# design.net
KiCad netlist of a schematic drawn in Altium Designer
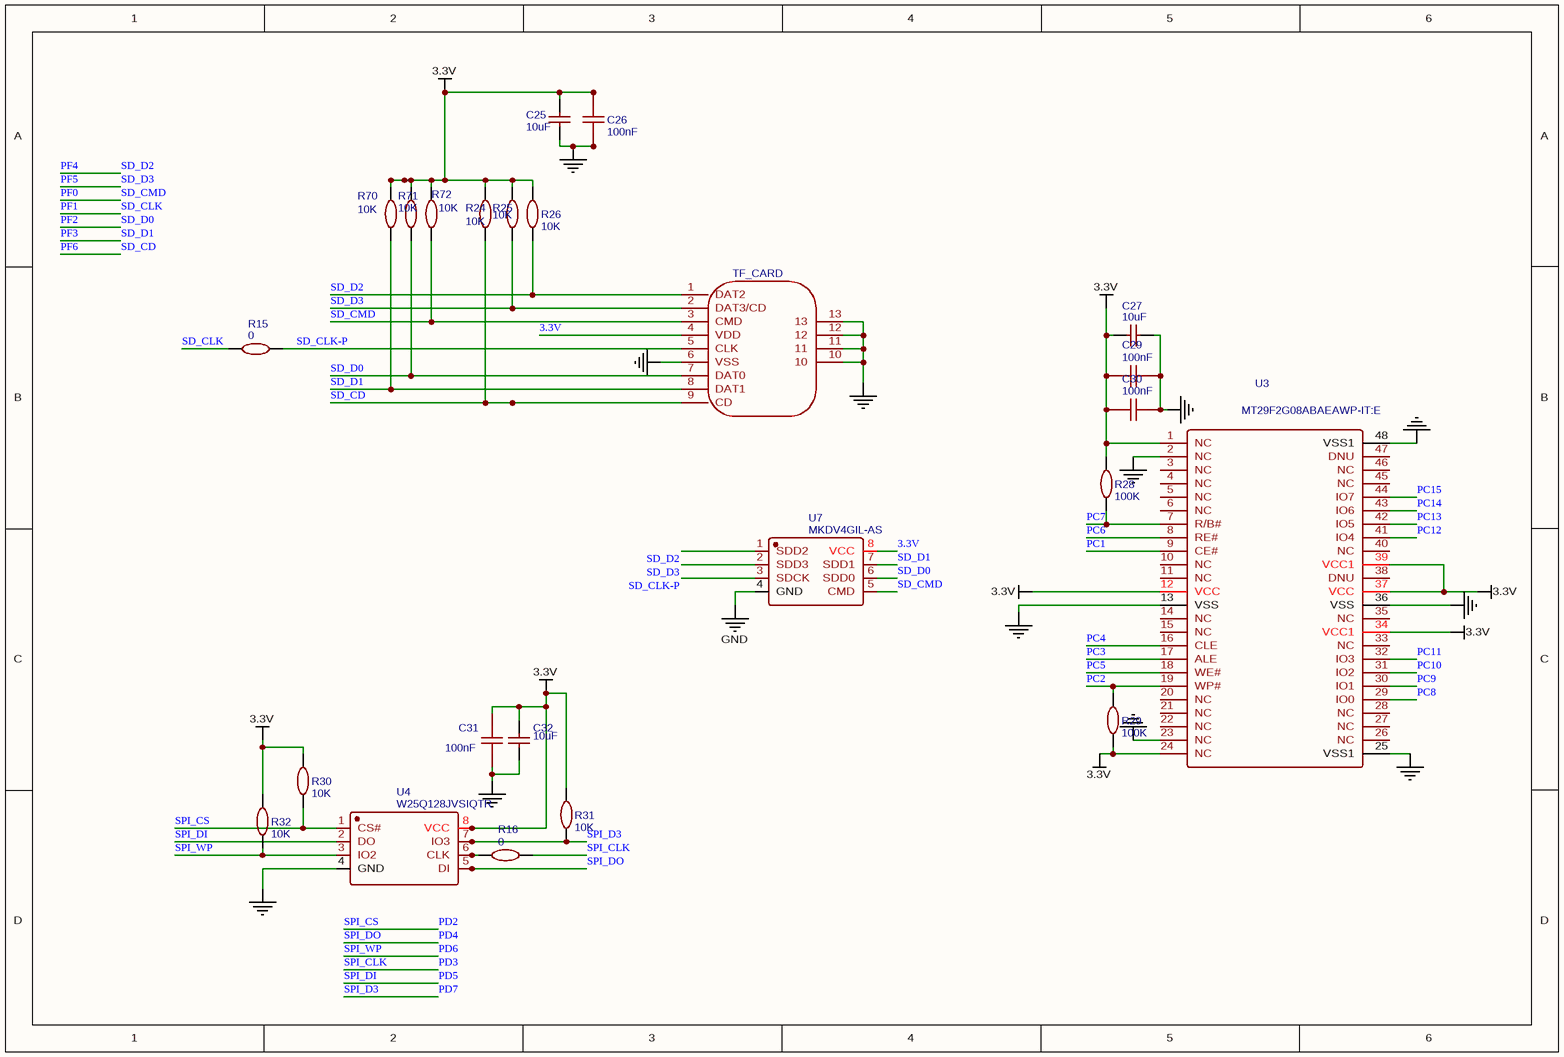
[diagram p0: 存储单元.schdoc]

(export (version "E")
  (design (tool "Eeschema 10.0.6"))
  (components
    (comp (ref "C25")
      (value "10uF")
      (footprint "0805")
      (fields
        (field (name "BOM_MANUFACTURER PART") "CL21A106KAYNNNE")
        (field (name "BOM_SUPPLIER PART") "C15850")
      )
      (libsource (lib "altium-import") (part "root_1_10uF_"))
    )
    (comp (ref "C26")
      (value "100nF")
      (footprint "0603")
      (fields
        (field (name "BOM_MANUFACTURER PART") "CC0603KRX7R9BB104")
        (field (name "BOM_SUPPLIER PART") "C14663")
      )
      (libsource (lib "altium-import") (part "root_1_100nF_"))
    )
    (comp (ref "C27")
      (value "10uF")
      (footprint "0805")
      (fields
        (field (name "BOM_MANUFACTURER PART") "CL21A106KAYNNNE")
        (field (name "BOM_SUPPLIER PART") "C15850")
      )
      (libsource (lib "altium-import") (part "root_2_10uF_"))
    )
    (comp (ref "C29")
      (value "100nF")
      (footprint "0603")
      (fields
        (field (name "BOM_MANUFACTURER PART") "CC0603KRX7R9BB104")
        (field (name "BOM_SUPPLIER PART") "C14663")
      )
      (libsource (lib "altium-import") (part "root_0_100nF_"))
    )
    (comp (ref "C30")
      (value "100nF")
      (footprint "0603")
      (fields
        (field (name "BOM_MANUFACTURER PART") "CC0603KRX7R9BB104")
        (field (name "BOM_SUPPLIER PART") "C14663")
      )
      (libsource (lib "altium-import") (part "root_2_100nF_"))
    )
    (comp (ref "C31")
      (value "100nF")
      (footprint "0603")
      (fields
        (field (name "BOM_MANUFACTURER PART") "CC0603KRX7R9BB104")
        (field (name "BOM_SUPPLIER PART") "C14663")
      )
      (libsource (lib "altium-import") (part "root_3_100nF_"))
    )
    (comp (ref "C32")
      (value "10uF")
      (footprint "0805")
      (fields
        (field (name "BOM_MANUFACTURER PART") "CL21A106KAYNNNE")
        (field (name "BOM_SUPPLIER PART") "C15850")
      )
      (libsource (lib "altium-import") (part "root_3_10uF_"))
    )
    (comp (ref "R15")
      (value "0")
      (footprint "0603")
      (fields
        (field (name "BOM_MANUFACTURER PART") "0603WAF0000T5E")
        (field (name "BOM_SUPPLIER PART") "C21189")
      )
      (libsource (lib "altium-import") (part "root_0_0_"))
    )
    (comp (ref "R16")
      (value "0")
      (footprint "0603")
      (fields
        (field (name "BOM_MANUFACTURER PART") "0603WAF0000T5E")
        (field (name "BOM_SUPPLIER PART") "C21189")
      )
      (libsource (lib "altium-import") (part "root_0_0_"))
    )
    (comp (ref "R24")
      (value "10K")
      (footprint "0603")
      (fields
        (field (name "BOM_MANUFACTURER PART") "0603WAF1002T5E")
        (field (name "BOM_SUPPLIER PART") "C25804")
      )
      (libsource (lib "altium-import") (part "root_1_10K_"))
    )
    (comp (ref "R25")
      (value "10K")
      (footprint "0603")
      (fields
        (field (name "BOM_MANUFACTURER PART") "0603WAF1002T5E")
        (field (name "BOM_SUPPLIER PART") "C25804")
      )
      (libsource (lib "altium-import") (part "root_1_10K_"))
    )
    (comp (ref "R26")
      (value "10K")
      (footprint "0603")
      (fields
        (field (name "BOM_MANUFACTURER PART") "0603WAF1002T5E")
        (field (name "BOM_SUPPLIER PART") "C25804")
      )
      (libsource (lib "altium-import") (part "root_1_10K_"))
    )
    (comp (ref "R28")
      (value "100K")
      (footprint "0603")
      (fields
        (field (name "BOM_MANUFACTURER PART") "0603WAF1003T5E")
        (field (name "BOM_SUPPLIER PART") "C25803")
      )
      (libsource (lib "altium-import") (part "root_1_100K_"))
    )
    (comp (ref "R29")
      (value "100K")
      (footprint "0603")
      (fields
        (field (name "BOM_MANUFACTURER PART") "0603WAF1003T5E")
        (field (name "BOM_SUPPLIER PART") "C25803")
      )
      (libsource (lib "altium-import") (part "root_1_100K_"))
    )
    (comp (ref "R30")
      (value "10K")
      (footprint "0603")
      (fields
        (field (name "BOM_MANUFACTURER PART") "0603WAF1002T5E")
        (field (name "BOM_SUPPLIER PART") "C25804")
      )
      (libsource (lib "altium-import") (part "root_1_10K_"))
    )
    (comp (ref "R31")
      (value "10K")
      (footprint "0603")
      (fields
        (field (name "BOM_MANUFACTURER PART") "0603WAF1002T5E")
        (field (name "BOM_SUPPLIER PART") "C25804")
      )
      (libsource (lib "altium-import") (part "root_1_10K_"))
    )
    (comp (ref "R32")
      (value "10K")
      (footprint "0603")
      (fields
        (field (name "BOM_MANUFACTURER PART") "0603WAF1002T5E")
        (field (name "BOM_SUPPLIER PART") "C25804")
      )
      (libsource (lib "altium-import") (part "root_1_10K_"))
    )
    (comp (ref "R70")
      (value "10K")
      (footprint "0603")
      (fields
        (field (name "BOM_MANUFACTURER PART") "0603WAF1002T5E")
        (field (name "BOM_SUPPLIER PART") "C25804")
      )
      (libsource (lib "altium-import") (part "root_1_10K_"))
    )
    (comp (ref "R71")
      (value "10K")
      (footprint "0603")
      (fields
        (field (name "BOM_MANUFACTURER PART") "0603WAF1002T5E")
        (field (name "BOM_SUPPLIER PART") "C25804")
      )
      (libsource (lib "altium-import") (part "root_1_10K_"))
    )
    (comp (ref "R72")
      (value "10K")
      (footprint "0603")
      (fields
        (field (name "BOM_MANUFACTURER PART") "0603WAF1002T5E")
        (field (name "BOM_SUPPLIER PART") "C25804")
      )
      (libsource (lib "altium-import") (part "root_1_10K_"))
    )
    (comp (ref "TF_CARD1")
      (value "TF_CARD")
      (footprint "TF-115_MRS")
      (fields
        (field (name "BOM_MANUFACTURER PART") "?")
        (field (name "BOM_SUPPLIER PART") "undefined")
        (field (name "CONTRIBUTOR") "ration")
      )
      (libsource (lib "altium-import") (part "root_0_TF_CARD_"))
    )
    (comp (ref "U3")
      (value "MT29F2G08ABAEAWP-IT:E")
      (footprint "TSOP-48")
      (fields (field (name "BOM_SUPPLIER PART") "C110896") (field (name "CONTRIBUTOR") "LCSC"))
      (libsource (lib "altium-import") (part "root_0_MT29F2G08ABAEAWP-IT{colon}E_"))
    )
    (comp (ref "U4")
      (value "W25Q128JVSIQTR")
      (footprint "SOIC-8_208MIL")
      (fields (field (name "BOM_SUPPLIER PART") "C97521"))
      (libsource (lib "altium-import") (part "root_0_W25Q128JVSIQTR_"))
    )
    (comp (ref "U7")
      (value "MKDV4GIL-AS")
      (footprint "LGA-8_8PIN-L6.10-W8.10-PITCH0.65-TL")
      (fields (field (name "BOM_SUPPLIER PART") "C379093") (field (name "CONTRIBUTOR") "LCSC"))
      (libsource (lib "altium-import") (part "root_0_MKDV4GIL-AS_"))
    )
  )
  (nets
    (net (code "1") (name "/PC1") (class "Default")
      (node (ref "U3") (pin "9") (pinfunction "CE#_9") (pintype "passive"))
    )
    (net (code "2") (name "/PC2") (class "Default")
      (node (ref "R29") (pin "2") (pinfunction "2_2") (pintype "passive"))
      (node (ref "U3") (pin "19") (pinfunction "WP#_19") (pintype "passive"))
    )
    (net (code "3") (name "/PC3") (class "Default")
      (node (ref "U3") (pin "17") (pinfunction "ALE_17") (pintype "passive"))
    )
    (net (code "4") (name "/PC4") (class "Default")
      (node (ref "U3") (pin "16") (pinfunction "CLE_16") (pintype "passive"))
    )
    (net (code "5") (name "/PC5") (class "Default")
      (node (ref "U3") (pin "18") (pinfunction "WE#_18") (pintype "passive"))
    )
    (net (code "6") (name "/PC6") (class "Default")
      (node (ref "U3") (pin "8") (pinfunction "RE#_8") (pintype "passive"))
    )
    (net (code "7") (name "/PC7") (class "Default")
      (node (ref "R28") (pin "1") (pinfunction "1_1") (pintype "passive"))
      (node (ref "U3") (pin "7") (pinfunction "R/B#_7") (pintype "passive"))
    )
    (net (code "8") (name "/PC8") (class "Default")
      (node (ref "U3") (pin "29") (pinfunction "IO0_29") (pintype "passive"))
    )
    (net (code "9") (name "/PC9") (class "Default")
      (node (ref "U3") (pin "30") (pinfunction "IO1_30") (pintype "passive"))
    )
    (net (code "10") (name "/PC10") (class "Default")
      (node (ref "U3") (pin "31") (pinfunction "IO2_31") (pintype "passive"))
    )
    (net (code "11") (name "/PC11") (class "Default")
      (node (ref "U3") (pin "32") (pinfunction "IO3_32") (pintype "passive"))
    )
    (net (code "12") (name "/PC12") (class "Default")
      (node (ref "U3") (pin "41") (pinfunction "IO4_41") (pintype "passive"))
    )
    (net (code "13") (name "/PC13") (class "Default")
      (node (ref "U3") (pin "42") (pinfunction "IO5_42") (pintype "passive"))
    )
    (net (code "14") (name "/PC14") (class "Default")
      (node (ref "U3") (pin "43") (pinfunction "IO6_43") (pintype "passive"))
    )
    (net (code "15") (name "/PC15") (class "Default")
      (node (ref "U3") (pin "44") (pinfunction "IO7_44") (pintype "passive"))
    )
    (net (code "16") (name "/PD2") (class "Default")
      (node (ref "R30") (pin "1") (pinfunction "1_1") (pintype "passive"))
      (node (ref "U4") (pin "1") (pinfunction "CS#_1") (pintype "passive"))
    )
    (net (code "17") (name "/PD3") (class "Default")
      (node (ref "R16") (pin "2") (pinfunction "2_2") (pintype "passive"))
    )
    (net (code "18") (name "/PD4") (class "Default")
      (node (ref "U4") (pin "5") (pinfunction "DI_5") (pintype "passive"))
    )
    (net (code "19") (name "/PD5") (class "Default")
      (node (ref "U4") (pin "2") (pinfunction "DO_2") (pintype "passive"))
    )
    (net (code "20") (name "/PD6") (class "Default")
      (node (ref "R32") (pin "1") (pinfunction "1_1") (pintype "passive"))
      (node (ref "U4") (pin "3") (pinfunction "IO2_3") (pintype "passive"))
    )
    (net (code "21") (name "/PD7") (class "Default")
      (node (ref "R31") (pin "1") (pinfunction "1_1") (pintype "passive"))
      (node (ref "U4") (pin "7") (pinfunction "IO3_7") (pintype "passive"))
    )
    (net (code "22") (name "/PF0") (class "Default")
      (node (ref "R72") (pin "1") (pinfunction "1_1") (pintype "passive"))
      (node (ref "TF_CARD1") (pin "3") (pinfunction "CMD_3") (pintype "passive"))
      (node (ref "U7") (pin "5") (pinfunction "CMD_5") (pintype "passive"))
    )
    (net (code "23") (name "/PF1") (class "Default")
      (node (ref "R15") (pin "1") (pinfunction "1_1") (pintype "passive"))
    )
    (net (code "24") (name "/PF2") (class "Default")
      (node (ref "R71") (pin "1") (pinfunction "1_1") (pintype "passive"))
      (node (ref "TF_CARD1") (pin "7") (pinfunction "DAT0_7") (pintype "passive"))
      (node (ref "U7") (pin "6") (pinfunction "SDD0_6") (pintype "passive"))
    )
    (net (code "25") (name "/PF3") (class "Default")
      (node (ref "R70") (pin "1") (pinfunction "1_1") (pintype "passive"))
      (node (ref "TF_CARD1") (pin "8") (pinfunction "DAT1_8") (pintype "passive"))
      (node (ref "U7") (pin "7") (pinfunction "SDD1_7") (pintype "passive"))
    )
    (net (code "26") (name "/PF4") (class "Default")
      (node (ref "R26") (pin "1") (pinfunction "1_1") (pintype "passive"))
      (node (ref "TF_CARD1") (pin "1") (pinfunction "DAT2_1") (pintype "passive"))
      (node (ref "U7") (pin "1") (pinfunction "SDD2_1") (pintype "passive"))
    )
    (net (code "27") (name "/PF5") (class "Default")
      (node (ref "R25") (pin "1") (pinfunction "1_1") (pintype "passive"))
      (node (ref "TF_CARD1") (pin "2") (pinfunction "DAT3/CD_2") (pintype "passive"))
      (node (ref "U7") (pin "2") (pinfunction "SDD3_2") (pintype "passive"))
    )
    (net (code "28") (name "/PF6") (class "Default")
      (node (ref "R24") (pin "1") (pinfunction "1_1") (pintype "passive"))
      (node (ref "TF_CARD1") (pin "9") (pinfunction "CD_9") (pintype "passive"))
    )
    (net (code "29") (name "/SD_CLK-P") (class "Default")
      (node (ref "R15") (pin "2") (pinfunction "2_2") (pintype "passive"))
      (node (ref "TF_CARD1") (pin "5") (pinfunction "CLK_5") (pintype "passive"))
      (node (ref "U7") (pin "3") (pinfunction "SDCK_3") (pintype "passive"))
    )
    (net (code "30") (name "3.3V") (class "Default")
      (node (ref "C25") (pin "2") (pinfunction "2_2") (pintype "passive"))
      (node (ref "C26") (pin "2") (pinfunction "2_2") (pintype "passive"))
      (node (ref "C27") (pin "2") (pinfunction "2_2") (pintype "passive"))
      (node (ref "C29") (pin "1") (pinfunction "1_1") (pintype "passive"))
      (node (ref "C30") (pin "2") (pinfunction "2_2") (pintype "passive"))
      (node (ref "C31") (pin "1") (pinfunction "1_1") (pintype "passive"))
      (node (ref "C32") (pin "1") (pinfunction "1_1") (pintype "passive"))
      (node (ref "R24") (pin "2") (pinfunction "2_2") (pintype "passive"))
      (node (ref "R25") (pin "2") (pinfunction "2_2") (pintype "passive"))
      (node (ref "R26") (pin "2") (pinfunction "2_2") (pintype "passive"))
      (node (ref "R28") (pin "2") (pinfunction "2_2") (pintype "passive"))
      (node (ref "R29") (pin "1") (pinfunction "1_1") (pintype "passive"))
      (node (ref "R30") (pin "2") (pinfunction "2_2") (pintype "passive"))
      (node (ref "R31") (pin "2") (pinfunction "2_2") (pintype "passive"))
      (node (ref "R32") (pin "2") (pinfunction "2_2") (pintype "passive"))
      (node (ref "R70") (pin "2") (pinfunction "2_2") (pintype "passive"))
      (node (ref "R71") (pin "2") (pinfunction "2_2") (pintype "passive"))
      (node (ref "R72") (pin "2") (pinfunction "2_2") (pintype "passive"))
      (node (ref "TF_CARD1") (pin "4") (pinfunction "VDD_4") (pintype "passive"))
      (node (ref "U3") (pin "1") (pinfunction "NC_1") (pintype "passive"))
      (node (ref "U3") (pin "12") (pinfunction "VCC_12") (pintype "passive"))
      (node (ref "U3") (pin "24") (pinfunction "NC_24") (pintype "passive"))
      (node (ref "U3") (pin "34") (pinfunction "VCC1_34") (pintype "passive"))
      (node (ref "U3") (pin "37") (pinfunction "VCC_37") (pintype "passive"))
      (node (ref "U3") (pin "39") (pinfunction "VCC1_39") (pintype "passive"))
      (node (ref "U4") (pin "8") (pinfunction "VCC_8") (pintype "passive"))
      (node (ref "U7") (pin "8") (pinfunction "VCC_8") (pintype "passive"))
    )
    (net (code "31") (name "GND") (class "Default")
      (node (ref "C25") (pin "1") (pinfunction "1_1") (pintype "passive"))
      (node (ref "C26") (pin "1") (pinfunction "1_1") (pintype "passive"))
      (node (ref "C27") (pin "1") (pinfunction "1_1") (pintype "passive"))
      (node (ref "C29") (pin "2") (pinfunction "2_2") (pintype "passive"))
      (node (ref "C30") (pin "1") (pinfunction "1_1") (pintype "passive"))
      (node (ref "C31") (pin "2") (pinfunction "2_2") (pintype "passive"))
      (node (ref "C32") (pin "2") (pinfunction "2_2") (pintype "passive"))
      (node (ref "TF_CARD1") (pin "10") (pinfunction "10_10") (pintype "passive"))
      (node (ref "TF_CARD1") (pin "11") (pinfunction "11_11") (pintype "passive"))
      (node (ref "TF_CARD1") (pin "12") (pinfunction "12_12") (pintype "passive"))
      (node (ref "TF_CARD1") (pin "13") (pinfunction "13_13") (pintype "passive"))
      (node (ref "TF_CARD1") (pin "6") (pinfunction "VSS_6") (pintype "passive"))
      (node (ref "U3") (pin "13") (pinfunction "VSS_13") (pintype "passive"))
      (node (ref "U3") (pin "2") (pinfunction "NC_2") (pintype "passive"))
      (node (ref "U3") (pin "23") (pinfunction "NC_23") (pintype "passive"))
      (node (ref "U3") (pin "25") (pinfunction "VSS1_25") (pintype "passive"))
      (node (ref "U3") (pin "36") (pinfunction "VSS_36") (pintype "passive"))
      (node (ref "U3") (pin "48") (pinfunction "VSS1_48") (pintype "passive"))
      (node (ref "U4") (pin "4") (pinfunction "GND_4") (pintype "passive"))
      (node (ref "U7") (pin "4") (pinfunction "GND_4") (pintype "passive"))
    )
    (net (code "32") (name "Net-(U4-CLK)") (class "Default")
      (node (ref "R16") (pin "1") (pinfunction "1_1") (pintype "passive"))
      (node (ref "U4") (pin "6") (pinfunction "CLK_6") (pintype "passive"))
    )
    (net (code "33") (name "unconnected-(U3-DNU-Pad38)") (class "Default")
      (node (ref "U3") (pin "38") (pinfunction "DNU_38") (pintype "passive"))
    )
    (net (code "34") (name "unconnected-(U3-DNU-Pad47)") (class "Default")
      (node (ref "U3") (pin "47") (pinfunction "DNU_47") (pintype "passive"))
    )
    (net (code "35") (name "unconnected-(U3-NC-Pad3)") (class "Default")
      (node (ref "U3") (pin "3") (pinfunction "NC_3") (pintype "passive"))
    )
    (net (code "36") (name "unconnected-(U3-NC-Pad4)") (class "Default")
      (node (ref "U3") (pin "4") (pinfunction "NC_4") (pintype "passive"))
    )
    (net (code "37") (name "unconnected-(U3-NC-Pad5)") (class "Default")
      (node (ref "U3") (pin "5") (pinfunction "NC_5") (pintype "passive"))
    )
    (net (code "38") (name "unconnected-(U3-NC-Pad6)") (class "Default")
      (node (ref "U3") (pin "6") (pinfunction "NC_6") (pintype "passive"))
    )
    (net (code "39") (name "unconnected-(U3-NC-Pad10)") (class "Default")
      (node (ref "U3") (pin "10") (pinfunction "NC_10") (pintype "passive"))
    )
    (net (code "40") (name "unconnected-(U3-NC-Pad11)") (class "Default")
      (node (ref "U3") (pin "11") (pinfunction "NC_11") (pintype "passive"))
    )
    (net (code "41") (name "unconnected-(U3-NC-Pad14)") (class "Default")
      (node (ref "U3") (pin "14") (pinfunction "NC_14") (pintype "passive"))
    )
    (net (code "42") (name "unconnected-(U3-NC-Pad15)") (class "Default")
      (node (ref "U3") (pin "15") (pinfunction "NC_15") (pintype "passive"))
    )
    (net (code "43") (name "unconnected-(U3-NC-Pad20)") (class "Default")
      (node (ref "U3") (pin "20") (pinfunction "NC_20") (pintype "passive"))
    )
    (net (code "44") (name "unconnected-(U3-NC-Pad21)") (class "Default")
      (node (ref "U3") (pin "21") (pinfunction "NC_21") (pintype "passive"))
    )
    (net (code "45") (name "unconnected-(U3-NC-Pad22)") (class "Default")
      (node (ref "U3") (pin "22") (pinfunction "NC_22") (pintype "passive"))
    )
    (net (code "46") (name "unconnected-(U3-NC-Pad26)") (class "Default")
      (node (ref "U3") (pin "26") (pinfunction "NC_26") (pintype "passive"))
    )
    (net (code "47") (name "unconnected-(U3-NC-Pad27)") (class "Default")
      (node (ref "U3") (pin "27") (pinfunction "NC_27") (pintype "passive"))
    )
    (net (code "48") (name "unconnected-(U3-NC-Pad28)") (class "Default")
      (node (ref "U3") (pin "28") (pinfunction "NC_28") (pintype "passive"))
    )
    (net (code "49") (name "unconnected-(U3-NC-Pad33)") (class "Default")
      (node (ref "U3") (pin "33") (pinfunction "NC_33") (pintype "passive"))
    )
    (net (code "50") (name "unconnected-(U3-NC-Pad35)") (class "Default")
      (node (ref "U3") (pin "35") (pinfunction "NC_35") (pintype "passive"))
    )
    (net (code "51") (name "unconnected-(U3-NC-Pad40)") (class "Default")
      (node (ref "U3") (pin "40") (pinfunction "NC_40") (pintype "passive"))
    )
    (net (code "52") (name "unconnected-(U3-NC-Pad45)") (class "Default")
      (node (ref "U3") (pin "45") (pinfunction "NC_45") (pintype "passive"))
    )
    (net (code "53") (name "unconnected-(U3-NC-Pad46)") (class "Default")
      (node (ref "U3") (pin "46") (pinfunction "NC_46") (pintype "passive"))
    )
  )
)
